# retainer_pnp_opt.net
KiCad netlist of a schematic drawn in EAGLE
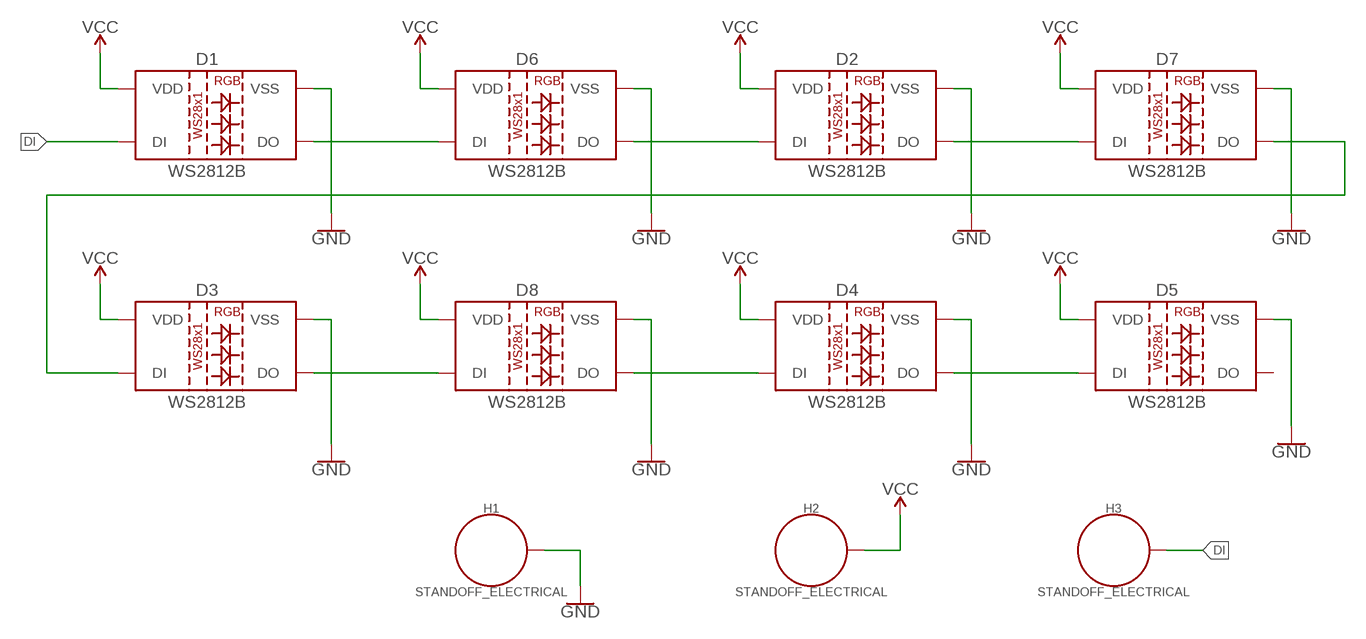
[diagram p0: schematic, sheet 1]

(export (version "E")
  (design (tool "Eeschema 10.0.6"))
  (components
    (comp (ref "D1")
      (value "WS2812B")
      (footprint "eagle-import:WS2812B")
      (libsource (lib "eagle-import") (part "WS2812B"))
    )
    (comp (ref "D2")
      (value "WS2812B")
      (footprint "eagle-import:WS2812B")
      (libsource (lib "eagle-import") (part "WS2812B"))
    )
    (comp (ref "D3")
      (value "WS2812B")
      (footprint "eagle-import:WS2812B")
      (libsource (lib "eagle-import") (part "WS2812B"))
    )
    (comp (ref "D4")
      (value "WS2812B")
      (footprint "eagle-import:WS2812B")
      (libsource (lib "eagle-import") (part "WS2812B"))
    )
    (comp (ref "D5")
      (value "WS2812B")
      (footprint "eagle-import:WS2812B")
      (libsource (lib "eagle-import") (part "WS2812B"))
    )
    (comp (ref "D6")
      (value "WS2812B")
      (footprint "eagle-import:WS2812B")
      (libsource (lib "eagle-import") (part "WS2812B"))
    )
    (comp (ref "D7")
      (value "WS2812B")
      (footprint "eagle-import:WS2812B")
      (libsource (lib "eagle-import") (part "WS2812B"))
    )
    (comp (ref "D8")
      (value "WS2812B")
      (footprint "eagle-import:WS2812B")
      (libsource (lib "eagle-import") (part "WS2812B"))
    )
    (comp (ref "H1")
      (value "STANDOFF_ELECTRICAL")
      (footprint "eagle-import:STANDOFF-ELECTRICAL")
      (libsource (lib "eagle-import") (part "STANDOFF_ELECTRICAL"))
    )
    (comp (ref "H2")
      (value "STANDOFF_ELECTRICAL")
      (footprint "eagle-import:STANDOFF-ELECTRICAL")
      (libsource (lib "eagle-import") (part "STANDOFF_ELECTRICAL"))
    )
    (comp (ref "H3")
      (value "STANDOFF_ELECTRICAL")
      (footprint "eagle-import:STANDOFF-ELECTRICAL")
      (libsource (lib "eagle-import") (part "STANDOFF_ELECTRICAL"))
    )
  )
  (nets
    (net (code "1") (name "DI") (class "Default")
      (node (ref "D1") (pin "4") (pinfunction "DI_4") (pintype "bidirectional"))
      (node (ref "H3") (pin "P1") (pinfunction "P$1_P1") (pintype "bidirectional"))
    )
    (net (code "2") (name "GND") (class "Default")
      (node (ref "D1") (pin "3") (pinfunction "VSS_3") (pintype "bidirectional"))
      (node (ref "D2") (pin "3") (pinfunction "VSS_3") (pintype "bidirectional"))
      (node (ref "D3") (pin "3") (pinfunction "VSS_3") (pintype "bidirectional"))
      (node (ref "D4") (pin "3") (pinfunction "VSS_3") (pintype "bidirectional"))
      (node (ref "D5") (pin "3") (pinfunction "VSS_3") (pintype "bidirectional"))
      (node (ref "D6") (pin "3") (pinfunction "VSS_3") (pintype "bidirectional"))
      (node (ref "D7") (pin "3") (pinfunction "VSS_3") (pintype "bidirectional"))
      (node (ref "D8") (pin "3") (pinfunction "VSS_3") (pintype "bidirectional"))
      (node (ref "H1") (pin "P1") (pinfunction "P$1_P1") (pintype "bidirectional"))
    )
    (net (code "3") (name "Net-(D1-DO)") (class "Default")
      (node (ref "D1") (pin "2") (pinfunction "DO_2") (pintype "bidirectional"))
      (node (ref "D6") (pin "4") (pinfunction "DI_4") (pintype "bidirectional"))
    )
    (net (code "4") (name "Net-(D2-DI)") (class "Default")
      (node (ref "D2") (pin "4") (pinfunction "DI_4") (pintype "bidirectional"))
      (node (ref "D6") (pin "2") (pinfunction "DO_2") (pintype "bidirectional"))
    )
    (net (code "5") (name "Net-(D2-DO)") (class "Default")
      (node (ref "D2") (pin "2") (pinfunction "DO_2") (pintype "bidirectional"))
      (node (ref "D7") (pin "4") (pinfunction "DI_4") (pintype "bidirectional"))
    )
    (net (code "6") (name "Net-(D3-DI)") (class "Default")
      (node (ref "D3") (pin "4") (pinfunction "DI_4") (pintype "bidirectional"))
      (node (ref "D7") (pin "2") (pinfunction "DO_2") (pintype "bidirectional"))
    )
    (net (code "7") (name "Net-(D3-DO)") (class "Default")
      (node (ref "D3") (pin "2") (pinfunction "DO_2") (pintype "bidirectional"))
      (node (ref "D8") (pin "4") (pinfunction "DI_4") (pintype "bidirectional"))
    )
    (net (code "8") (name "Net-(D4-DI)") (class "Default")
      (node (ref "D4") (pin "4") (pinfunction "DI_4") (pintype "bidirectional"))
      (node (ref "D8") (pin "2") (pinfunction "DO_2") (pintype "bidirectional"))
    )
    (net (code "9") (name "Net-(D4-DO)") (class "Default")
      (node (ref "D4") (pin "2") (pinfunction "DO_2") (pintype "bidirectional"))
      (node (ref "D5") (pin "4") (pinfunction "DI_4") (pintype "bidirectional"))
    )
    (net (code "10") (name "VCC") (class "Default")
      (node (ref "D1") (pin "1") (pinfunction "VDD_1") (pintype "bidirectional"))
      (node (ref "D2") (pin "1") (pinfunction "VDD_1") (pintype "bidirectional"))
      (node (ref "D3") (pin "1") (pinfunction "VDD_1") (pintype "bidirectional"))
      (node (ref "D4") (pin "1") (pinfunction "VDD_1") (pintype "bidirectional"))
      (node (ref "D5") (pin "1") (pinfunction "VDD_1") (pintype "bidirectional"))
      (node (ref "D6") (pin "1") (pinfunction "VDD_1") (pintype "bidirectional"))
      (node (ref "D7") (pin "1") (pinfunction "VDD_1") (pintype "bidirectional"))
      (node (ref "D8") (pin "1") (pinfunction "VDD_1") (pintype "bidirectional"))
      (node (ref "H2") (pin "P1") (pinfunction "P$1_P1") (pintype "bidirectional"))
    )
    (net (code "11") (name "unconnected-(D5-DO-Pad2)") (class "Default")
      (node (ref "D5") (pin "2") (pinfunction "DO_2") (pintype "bidirectional"))
    )
  )
)
